# Emitter.net
KiCad netlist of a schematic drawn in Altium Designer
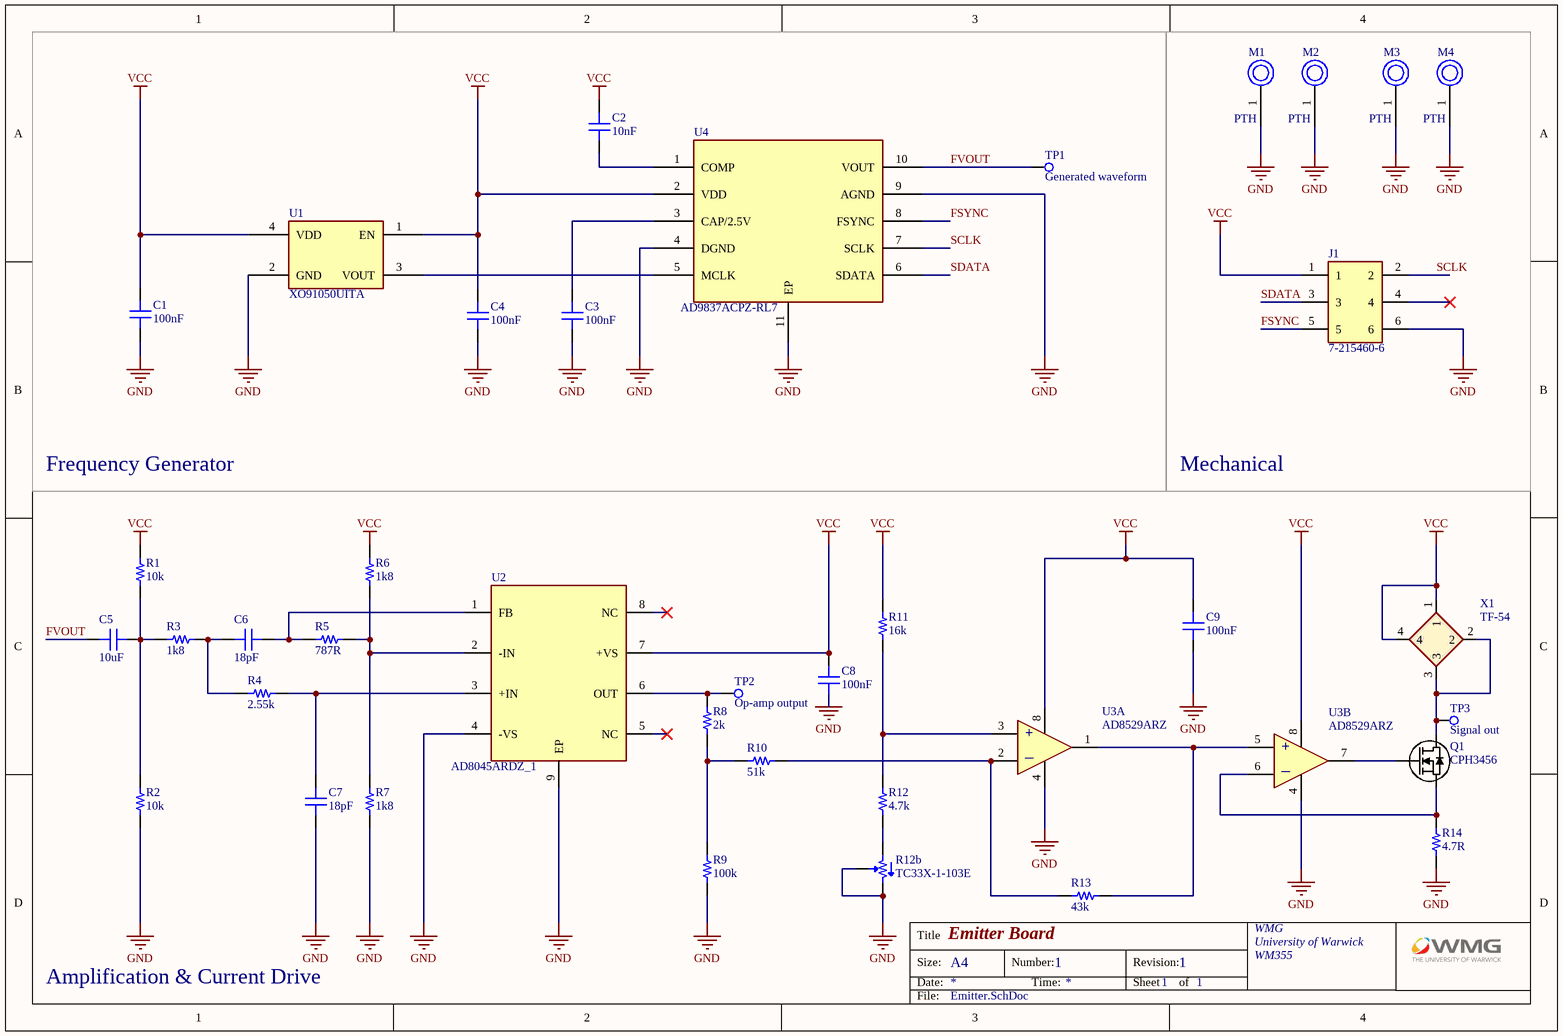
[diagram p0: Emitter.SchDoc]

(export (version "E")
  (design (tool "Eeschema 10.0.6"))
  (components
    (comp (ref "C1")
      (value "100nF")
      (footprint "CAP 0603_1608")
      (description "SMT Capacitor")
      (libsource (lib "BOJIT-Altium") (part "Capacitor"))
    )
    (comp (ref "C2")
      (value "10nF")
      (footprint "CAP 0603_1608")
      (description "SMT Capacitor")
      (libsource (lib "BOJIT-Altium") (part "Capacitor"))
    )
    (comp (ref "C3")
      (value "100nF")
      (footprint "CAP 0603_1608")
      (description "SMT Capacitor")
      (libsource (lib "BOJIT-Altium") (part "Capacitor"))
    )
    (comp (ref "C4")
      (value "100nF")
      (footprint "CAP 0603_1608")
      (description "SMT Capacitor")
      (libsource (lib "BOJIT-Altium") (part "Capacitor"))
    )
    (comp (ref "C5")
      (value "10uF")
      (footprint "CAP 0603_1608")
      (description "SMT Capacitor")
      (libsource (lib "BOJIT-Altium") (part "Capacitor"))
    )
    (comp (ref "C6")
      (value "18pF")
      (footprint "CAP 0603_1608")
      (description "SMT Capacitor")
      (libsource (lib "BOJIT-Altium") (part "Capacitor"))
    )
    (comp (ref "C7")
      (value "18pF")
      (footprint "CAP 0603_1608")
      (description "SMT Capacitor")
      (libsource (lib "BOJIT-Altium") (part "Capacitor"))
    )
    (comp (ref "C8")
      (value "100nF")
      (footprint "CAP 0603_1608")
      (description "SMT Capacitor")
      (libsource (lib "BOJIT-Altium") (part "Capacitor"))
    )
    (comp (ref "C9")
      (value "100nF")
      (footprint "CAP 0603_1608")
      (description "SMT Capacitor")
      (libsource (lib "BOJIT-Altium") (part "Capacitor"))
    )
    (comp (ref "J1")
      (value "7-215460-6")
      (footprint "WM355-Altium:72154606")
      (description "Micro-Match Connector Female 6-Way")
      (fields (field (name "MOUSER PART NUMBER") "571-7-215460-6"))
      (libsource (lib "WM355-Altium") (part "7-215460-6"))
    )
    (comp (ref "M1")
      (value "PTH")
      (footprint "WM355-Altium:M2-PTH")
      (description "Mounting Hole (Plated, Exposed Pad)")
      (libsource (lib "WM355-Altium") (part "PTH"))
    )
    (comp (ref "M2")
      (value "PTH")
      (footprint "WM355-Altium:M2-PTH")
      (description "Mounting Hole (Plated, Exposed Pad)")
      (libsource (lib "WM355-Altium") (part "PTH"))
    )
    (comp (ref "M3")
      (value "PTH")
      (footprint "WM355-Altium:M2-PTH")
      (description "Mounting Hole (Plated, Exposed Pad)")
      (libsource (lib "WM355-Altium") (part "PTH"))
    )
    (comp (ref "M4")
      (value "PTH")
      (footprint "WM355-Altium:M2-PTH")
      (description "Mounting Hole (Plated, Exposed Pad)")
      (libsource (lib "WM355-Altium") (part "PTH"))
    )
    (comp (ref "Q1")
      (value "CPH3456")
      (footprint "CPH3456")
      (description "N channel MOSFET")
      (libsource (lib "WM355-Altium") (part "CPH3456"))
    )
    (comp (ref "R1")
      (value "10k")
      (footprint "RES 0603_1608")
      (description "SMT Resistor")
      (libsource (lib "BOJIT-Altium") (part "Resistor"))
    )
    (comp (ref "R2")
      (value "10k")
      (footprint "RES 0603_1608")
      (description "SMT Resistor")
      (libsource (lib "BOJIT-Altium") (part "Resistor"))
    )
    (comp (ref "R3")
      (value "1k8")
      (footprint "RES 0603_1608")
      (description "SMT Resistor")
      (libsource (lib "BOJIT-Altium") (part "Resistor"))
    )
    (comp (ref "R4")
      (value "2.55k")
      (footprint "RES 0603_1608")
      (description "SMT Resistor")
      (libsource (lib "BOJIT-Altium") (part "Resistor"))
    )
    (comp (ref "R5")
      (value "787R")
      (footprint "RES 0603_1608")
      (description "SMT Resistor")
      (libsource (lib "BOJIT-Altium") (part "Resistor"))
    )
    (comp (ref "R6")
      (value "1k8")
      (footprint "RES 0603_1608")
      (description "SMT Resistor")
      (libsource (lib "BOJIT-Altium") (part "Resistor"))
    )
    (comp (ref "R7")
      (value "1k8")
      (footprint "RES 0603_1608")
      (description "SMT Resistor")
      (libsource (lib "BOJIT-Altium") (part "Resistor"))
    )
    (comp (ref "R8")
      (value "2k")
      (footprint "RES 0603_1608")
      (description "SMT Resistor")
      (libsource (lib "BOJIT-Altium") (part "Resistor"))
    )
    (comp (ref "R9")
      (value "100k")
      (footprint "RES 0603_1608")
      (description "SMT Resistor")
      (libsource (lib "BOJIT-Altium") (part "Resistor"))
    )
    (comp (ref "R10")
      (value "51k")
      (footprint "RES 0603_1608")
      (description "SMT Resistor")
      (libsource (lib "BOJIT-Altium") (part "Resistor"))
    )
    (comp (ref "R11")
      (value "16k")
      (footprint "RES 0603_1608")
      (description "SMT Resistor")
      (libsource (lib "BOJIT-Altium") (part "Resistor"))
    )
    (comp (ref "R12")
      (value "4.7k")
      (footprint "RES 0603_1608")
      (description "SMT Resistor")
      (libsource (lib "BOJIT-Altium") (part "Resistor"))
    )
    (comp (ref "R12b")
      (value "TC33X-1-103E")
      (footprint "WM355-Altium:TC33X2201E")
      (description "SMD Trim Potentiometer")
      (fields (field (name "MOUSER PART NUMBER") "652-TC33X-1-103E"))
      (libsource (lib "WM355-Altium") (part "TC33X-1-103E"))
    )
    (comp (ref "R13")
      (value "43k")
      (footprint "RES 0603_1608")
      (description "SMT Resistor")
      (libsource (lib "BOJIT-Altium") (part "Resistor"))
    )
    (comp (ref "R14")
      (value "4.7R")
      (footprint "RES 0805_2012")
      (description "SMT Resistor")
      (libsource (lib "BOJIT-Altium") (part "Resistor"))
    )
    (comp (ref "TP1")
      (value "Generated waveform")
      (footprint "TP-SMD-50mil")
      (libsource (lib "BOJIT-Altium") (part "Test Point"))
    )
    (comp (ref "TP2")
      (value "Op-amp output")
      (footprint "TP-SMD-50mil")
      (libsource (lib "BOJIT-Altium") (part "Test Point"))
    )
    (comp (ref "TP3")
      (value "Signal out")
      (footprint "TP-SMD-50mil")
      (libsource (lib "BOJIT-Altium") (part "Test Point"))
    )
    (comp (ref "U1")
      (value "XO91050UITA")
      (footprint "WM355-Altium:XO91050UITA24576")
      (description "16 MHz SMD oscillator")
      (fields (field (name "MANUFACTURER_PART_NUMBER") "14.7456MHZ XO91050UITA"))
      (libsource (lib "WM355-Altium") (part "16MHZ_XO91050UITA"))
    )
    (comp (ref "U2")
      (value "AD8045ARDZ_1")
      (footprint "WM355-Altium:SOIC127P600X175-9N")
      (description "High speed op-amp")
      (fields
        (field (name "MANUFACTURER_PART_NUMBER") "AD8045ARDZ")
        (field (name "MOUSER PART NUMBER") "584-AD8045ARDZ")
      )
      (libsource (lib "WM355-Altium") (part "AD8045ARDZ"))
    )
    (comp (ref "U3")
      (value "AD8529ARZ")
      (footprint "AD8529ARZ")
      (description "Op-amp")
      (libsource (lib "WM355-Altium") (part "AD8529ARZ"))
    )
    (comp (ref "U4")
      (value "AD9837ACPZ-RL7")
      (footprint "AD9837ACPZ-RL7")
      (description "Programmable waveform generator")
      (libsource (lib "WM355-Altium") (part "AD9837ACPZ-RL7"))
    )
    (comp (ref "X1")
      (value "TF-54")
      (footprint "WM355-Altium:TF-54")
      (description "TF-54 Socket from Fischer Elektronik")
      (libsource (lib "WM355-Altium") (part "TF-54"))
    )
  )
  (nets
    (net (code "1") (name "/FSYNC") (class "Default")
      (node (ref "J1") (pin "5") (pinfunction "5_5") (pintype "passive"))
      (node (ref "U4") (pin "8") (pinfunction "FSYNC_8") (pintype "passive"))
    )
    (net (code "2") (name "/FVOUT") (class "Default")
      (node (ref "C5") (pin "1") (pinfunction "1_1") (pintype "passive"))
      (node (ref "TP1") (pin "1") (pinfunction "TP_1") (pintype "passive"))
      (node (ref "U4") (pin "10") (pinfunction "VOUT_10") (pintype "passive"))
    )
    (net (code "3") (name "/SCLK") (class "Default")
      (node (ref "J1") (pin "2") (pinfunction "2_2") (pintype "passive"))
      (node (ref "U4") (pin "7") (pinfunction "SCLK_7") (pintype "passive"))
    )
    (net (code "4") (name "/SDATA") (class "Default")
      (node (ref "J1") (pin "3") (pinfunction "3_3") (pintype "passive"))
      (node (ref "U4") (pin "6") (pinfunction "SDATA_6") (pintype "passive"))
    )
    (net (code "5") (name "GND") (class "Default")
      (node (ref "C1") (pin "1") (pinfunction "1_1") (pintype "passive"))
      (node (ref "C3") (pin "1") (pinfunction "1_1") (pintype "passive"))
      (node (ref "C4") (pin "1") (pinfunction "1_1") (pintype "passive"))
      (node (ref "C7") (pin "1") (pinfunction "1_1") (pintype "passive"))
      (node (ref "C8") (pin "1") (pinfunction "1_1") (pintype "passive"))
      (node (ref "C9") (pin "1") (pinfunction "1_1") (pintype "passive"))
      (node (ref "J1") (pin "6") (pinfunction "6_6") (pintype "passive"))
      (node (ref "M1") (pin "1") (pinfunction "1_1") (pintype "passive"))
      (node (ref "M2") (pin "1") (pinfunction "1_1") (pintype "passive"))
      (node (ref "M3") (pin "1") (pinfunction "1_1") (pintype "passive"))
      (node (ref "M4") (pin "1") (pinfunction "1_1") (pintype "passive"))
      (node (ref "R12b") (pin "2") (pinfunction "WIPER_2") (pintype "passive"))
      (node (ref "R12b") (pin "3") (pinfunction "CW_3") (pintype "passive"))
      (node (ref "R14") (pin "1") (pinfunction "1_1") (pintype "passive"))
      (node (ref "R2") (pin "1") (pinfunction "1_1") (pintype "passive"))
      (node (ref "R7") (pin "1") (pinfunction "1_1") (pintype "passive"))
      (node (ref "R9") (pin "1") (pinfunction "1_1") (pintype "passive"))
      (node (ref "U1") (pin "2") (pinfunction "GND_2") (pintype "passive"))
      (node (ref "U2") (pin "4") (pinfunction "-VS_4") (pintype "passive"))
      (node (ref "U2") (pin "9") (pinfunction "EP_9") (pintype "passive"))
      (node (ref "U3") (pin "4") (pinfunction "V-_4") (pintype "power_in"))
      (node (ref "U4") (pin "11") (pinfunction "EP_11") (pintype "passive"))
      (node (ref "U4") (pin "4") (pinfunction "DGND_4") (pintype "passive"))
      (node (ref "U4") (pin "9") (pinfunction "AGND_9") (pintype "passive"))
    )
    (net (code "6") (name "Net-(C5-Pad2)") (class "Default")
      (node (ref "C5") (pin "2") (pinfunction "2_2") (pintype "passive"))
      (node (ref "R1") (pin "1") (pinfunction "1_1") (pintype "passive"))
      (node (ref "R2") (pin "2") (pinfunction "2_2") (pintype "passive"))
      (node (ref "R3") (pin "1") (pinfunction "1_1") (pintype "passive"))
    )
    (net (code "7") (name "Net-(C6-Pad1)") (class "Default")
      (node (ref "C6") (pin "1") (pinfunction "1_1") (pintype "passive"))
      (node (ref "R3") (pin "2") (pinfunction "2_2") (pintype "passive"))
      (node (ref "R4") (pin "1") (pinfunction "1_1") (pintype "passive"))
    )
    (net (code "8") (name "Net-(Q1-D)") (class "Default")
      (node (ref "Q1") (pin "2") (pinfunction "D_2") (pintype "passive"))
      (node (ref "TP3") (pin "1") (pinfunction "TP_1") (pintype "passive"))
      (node (ref "X1") (pin "2") (pinfunction "2_2") (pintype "passive"))
      (node (ref "X1") (pin "3") (pinfunction "3_3") (pintype "passive"))
    )
    (net (code "9") (name "Net-(Q1-G)") (class "Default")
      (node (ref "Q1") (pin "1") (pinfunction "G_1") (pintype "passive"))
      (node (ref "U3") (pin "7") (pinfunction "OUT_B_7") (pintype "passive"))
    )
    (net (code "10") (name "Net-(Q1-S)") (class "Default")
      (node (ref "Q1") (pin "3") (pinfunction "S_3") (pintype "passive"))
      (node (ref "R14") (pin "2") (pinfunction "2_2") (pintype "passive"))
      (node (ref "U3") (pin "6") (pinfunction "-IN_B_6") (pintype "passive"))
    )
    (net (code "11") (name "Net-(R10-Pad1)") (class "Default")
      (node (ref "R10") (pin "1") (pinfunction "1_1") (pintype "passive"))
      (node (ref "R8") (pin "1") (pinfunction "1_1") (pintype "passive"))
      (node (ref "R9") (pin "2") (pinfunction "2_2") (pintype "passive"))
    )
    (net (code "12") (name "Net-(R12b-CCW)") (class "Default")
      (node (ref "R12") (pin "1") (pinfunction "1_1") (pintype "passive"))
      (node (ref "R12b") (pin "1") (pinfunction "CCW_1") (pintype "passive"))
    )
    (net (code "13") (name "Net-(TP2-TP)") (class "Default")
      (node (ref "R8") (pin "2") (pinfunction "2_2") (pintype "passive"))
      (node (ref "TP2") (pin "1") (pinfunction "TP_1") (pintype "passive"))
      (node (ref "U2") (pin "6") (pinfunction "OUT_6") (pintype "passive"))
    )
    (net (code "14") (name "Net-(U1-VOUT)") (class "Default")
      (node (ref "U1") (pin "3") (pinfunction "VOUT_3") (pintype "passive"))
      (node (ref "U4") (pin "5") (pinfunction "MCLK_5") (pintype "passive"))
    )
    (net (code "15") (name "Net-(U2-+IN)") (class "Default")
      (node (ref "C7") (pin "2") (pinfunction "2_2") (pintype "passive"))
      (node (ref "R4") (pin "2") (pinfunction "2_2") (pintype "passive"))
      (node (ref "U2") (pin "3") (pinfunction "+IN_3") (pintype "passive"))
    )
    (net (code "16") (name "Net-(U2--IN)") (class "Default")
      (node (ref "R5") (pin "2") (pinfunction "2_2") (pintype "passive"))
      (node (ref "R6") (pin "1") (pinfunction "1_1") (pintype "passive"))
      (node (ref "R7") (pin "2") (pinfunction "2_2") (pintype "passive"))
      (node (ref "U2") (pin "2") (pinfunction "-IN_2") (pintype "passive"))
    )
    (net (code "17") (name "Net-(U2-FB)") (class "Default")
      (node (ref "C6") (pin "2") (pinfunction "2_2") (pintype "passive"))
      (node (ref "R5") (pin "1") (pinfunction "1_1") (pintype "passive"))
      (node (ref "U2") (pin "1") (pinfunction "FB_1") (pintype "passive"))
    )
    (net (code "18") (name "Net-(U3A-+IN_A)") (class "Default")
      (node (ref "R11") (pin "1") (pinfunction "1_1") (pintype "passive"))
      (node (ref "R12") (pin "2") (pinfunction "2_2") (pintype "passive"))
      (node (ref "U3") (pin "3") (pinfunction "+IN_A_3") (pintype "passive"))
    )
    (net (code "19") (name "Net-(U3A--IN_A)") (class "Default")
      (node (ref "R10") (pin "2") (pinfunction "2_2") (pintype "passive"))
      (node (ref "R13") (pin "1") (pinfunction "1_1") (pintype "passive"))
      (node (ref "U3") (pin "2") (pinfunction "-IN_A_2") (pintype "passive"))
    )
    (net (code "20") (name "Net-(U3A-OUT_A)") (class "Default")
      (node (ref "R13") (pin "2") (pinfunction "2_2") (pintype "passive"))
      (node (ref "U3") (pin "1") (pinfunction "OUT_A_1") (pintype "passive"))
      (node (ref "U3") (pin "5") (pinfunction "+IN_B_5") (pintype "passive"))
    )
    (net (code "21") (name "Net-(U4-CAP{slash}2.5V)") (class "Default")
      (node (ref "C3") (pin "2") (pinfunction "2_2") (pintype "passive"))
      (node (ref "U4") (pin "3") (pinfunction "CAP/2.5V_3") (pintype "passive"))
    )
    (net (code "22") (name "Net-(U4-COMP)") (class "Default")
      (node (ref "C2") (pin "1") (pinfunction "1_1") (pintype "passive"))
      (node (ref "U4") (pin "1") (pinfunction "COMP_1") (pintype "passive"))
    )
    (net (code "23") (name "VCC") (class "Default")
      (node (ref "C1") (pin "2") (pinfunction "2_2") (pintype "passive"))
      (node (ref "C2") (pin "2") (pinfunction "2_2") (pintype "passive"))
      (node (ref "C4") (pin "2") (pinfunction "2_2") (pintype "passive"))
      (node (ref "C8") (pin "2") (pinfunction "2_2") (pintype "passive"))
      (node (ref "C9") (pin "2") (pinfunction "2_2") (pintype "passive"))
      (node (ref "J1") (pin "1") (pinfunction "1_1") (pintype "passive"))
      (node (ref "R1") (pin "2") (pinfunction "2_2") (pintype "passive"))
      (node (ref "R11") (pin "2") (pinfunction "2_2") (pintype "passive"))
      (node (ref "R6") (pin "2") (pinfunction "2_2") (pintype "passive"))
      (node (ref "U1") (pin "1") (pinfunction "EN_1") (pintype "passive"))
      (node (ref "U1") (pin "4") (pinfunction "VDD_4") (pintype "passive"))
      (node (ref "U2") (pin "7") (pinfunction "+VS_7") (pintype "passive"))
      (node (ref "U3") (pin "8") (pinfunction "V+_8") (pintype "power_in"))
      (node (ref "U4") (pin "2") (pinfunction "VDD_2") (pintype "passive"))
      (node (ref "X1") (pin "1") (pinfunction "1_1") (pintype "passive"))
      (node (ref "X1") (pin "4") (pinfunction "4_4") (pintype "passive"))
    )
    (net (code "24") (name "unconnected-(J1-Pad4)") (class "Default")
      (node (ref "J1") (pin "4") (pinfunction "4_4") (pintype "passive+no_connect"))
    )
    (net (code "25") (name "unconnected-(U2-NC-Pad5)") (class "Default")
      (node (ref "U2") (pin "5") (pinfunction "NC_5") (pintype "passive+no_connect"))
    )
    (net (code "26") (name "unconnected-(U2-NC-Pad8)") (class "Default")
      (node (ref "U2") (pin "8") (pinfunction "NC_8") (pintype "passive+no_connect"))
    )
  )
)
